# Paulo_V2.net
KiCad netlist of a schematic drawn in EAGLE
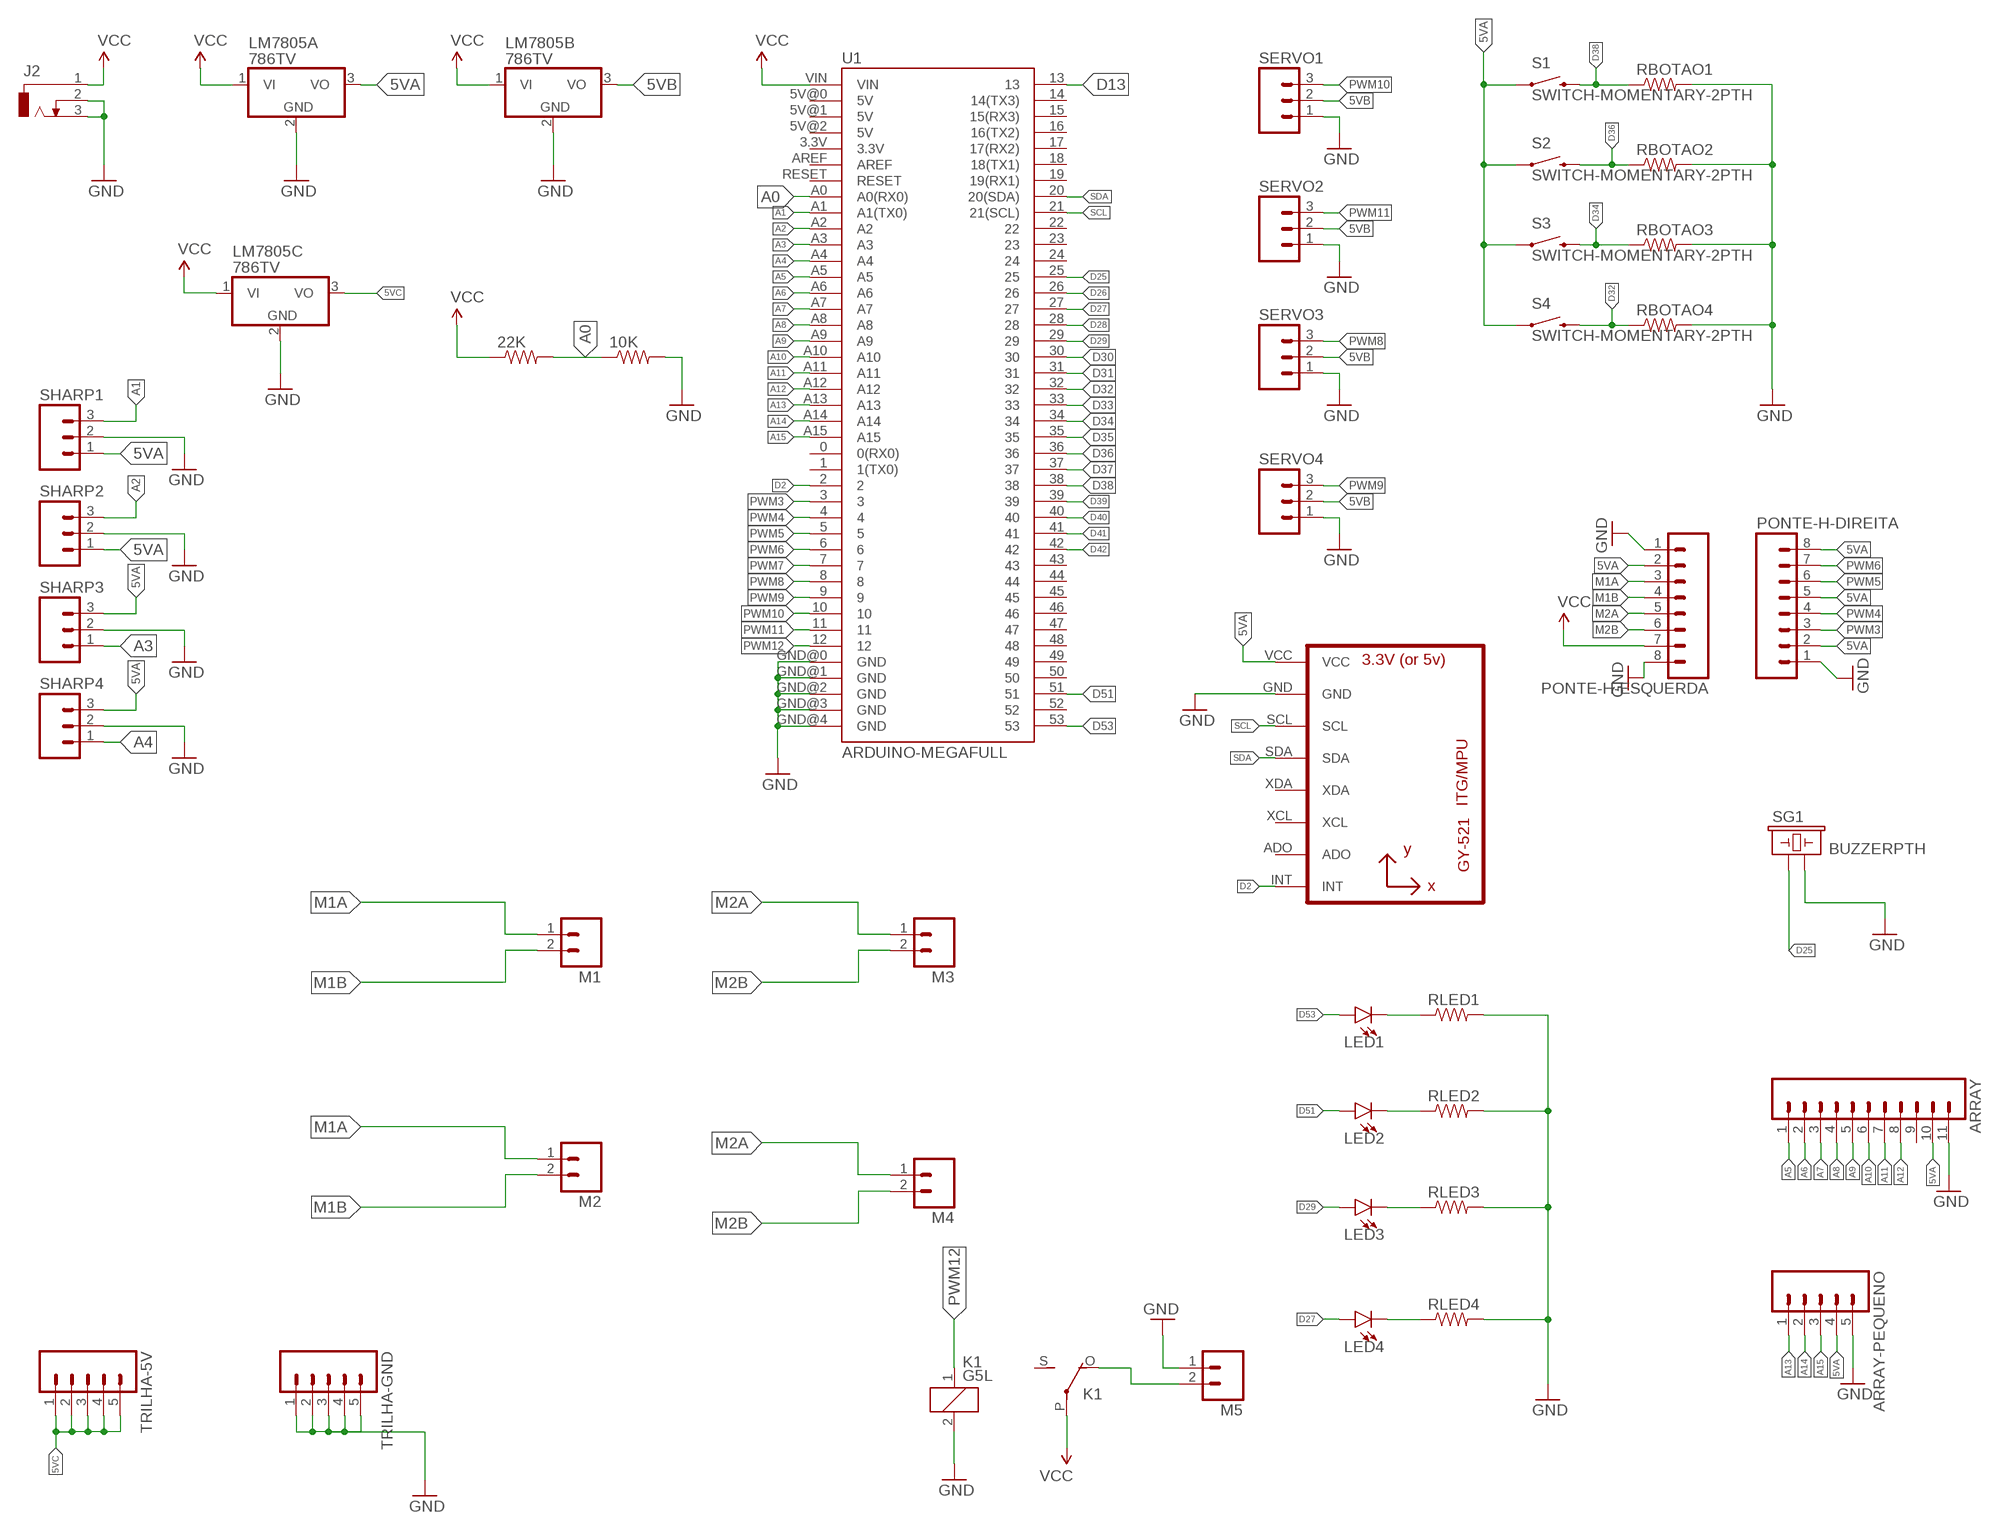
[diagram p0: schematic, sheet 1]

(export (version "E")
  (design (tool "Eeschema 10.0.6"))
  (components
    (comp (ref "10K")
      (value "RESISTOREZ")
      (footprint "eagle-import:AXIAL-0.3EZ")
      (libsource (lib "eagle-import") (part "RESISTOREZ"))
    )
    (comp (ref "22K")
      (value "RESISTOREZ")
      (footprint "eagle-import:AXIAL-0.3EZ")
      (libsource (lib "eagle-import") (part "RESISTOREZ"))
    )
    (comp (ref "ARRAY")
      (value "M11POGOPIN_HOLES_ONLY")
      (footprint "eagle-import:1X11_HOLES_ONLY")
      (libsource (lib "eagle-import") (part "M11POGOPIN_HOLES_ONLY"))
    )
    (comp (ref "ARRAY-PEQUENO")
      (value "M05PTH")
      (footprint "eagle-import:1X05")
      (libsource (lib "eagle-import") (part "M05PTH"))
    )
    (comp (ref "J2")
      (value "DCJ0303")
      (footprint "eagle-import:DCJ0303")
      (libsource (lib "eagle-import") (part "DCJ0303"))
    )
    (comp (ref "K1")
      (value "G5L")
      (footprint "eagle-import:G5LE")
      (libsource (lib "eagle-import") (part "G5L"))
    )
    (comp (ref "LED1")
      (value "LED5MM")
      (footprint "eagle-import:LED_5MM")
      (libsource (lib "eagle-import") (part "LED5MM"))
    )
    (comp (ref "LED2")
      (value "LED5MM")
      (footprint "eagle-import:LED_5MM")
      (libsource (lib "eagle-import") (part "LED5MM"))
    )
    (comp (ref "LED3")
      (value "LED5MM")
      (footprint "eagle-import:LED_5MM")
      (libsource (lib "eagle-import") (part "LED5MM"))
    )
    (comp (ref "LED4")
      (value "LED5MM")
      (footprint "eagle-import:LED_5MM")
      (libsource (lib "eagle-import") (part "LED5MM"))
    )
    (comp (ref "LM7805A")
      (value "786TV")
      (footprint "eagle-import:TO220V")
      (libsource (lib "eagle-import") (part "78TV6"))
    )
    (comp (ref "LM7805B")
      (value "786TV")
      (footprint "eagle-import:TO220V")
      (libsource (lib "eagle-import") (part "78TV6"))
    )
    (comp (ref "LM7805C")
      (value "786TV")
      (footprint "eagle-import:TO220V")
      (libsource (lib "eagle-import") (part "78TV6"))
    )
    (comp (ref "M1")
      (value "M02JST-PTH-VERT")
      (footprint "eagle-import:JST-2-PTH-VERT")
      (libsource (lib "eagle-import") (part "M02JST-PTH-VERT"))
    )
    (comp (ref "M2")
      (value "M02JST-PTH-VERT")
      (footprint "eagle-import:JST-2-PTH-VERT")
      (libsource (lib "eagle-import") (part "M02JST-PTH-VERT"))
    )
    (comp (ref "M3")
      (value "M02JST-PTH-VERT")
      (footprint "eagle-import:JST-2-PTH-VERT")
      (libsource (lib "eagle-import") (part "M02JST-PTH-VERT"))
    )
    (comp (ref "M4")
      (value "M02JST-PTH-VERT")
      (footprint "eagle-import:JST-2-PTH-VERT")
      (libsource (lib "eagle-import") (part "M02JST-PTH-VERT"))
    )
    (comp (ref "M5")
      (value "M02JST-PTH-VERT")
      (footprint "eagle-import:JST-2-PTH-VERT")
      (libsource (lib "eagle-import") (part "M02JST-PTH-VERT"))
    )
    (comp (ref "PONTE-H-DIREITA")
      (value "M08NO_SILK")
      (footprint "eagle-import:1X08_PIN1_NO_SILK")
      (libsource (lib "eagle-import") (part "M08NO_SILK"))
    )
    (comp (ref "PONTE-H-ESQUERDA")
      (value "M08NO_SILK")
      (footprint "eagle-import:1X08_PIN1_NO_SILK")
      (libsource (lib "eagle-import") (part "M08NO_SILK"))
    )
    (comp (ref "RBOTAO1")
      (value "RESISTOREZ")
      (footprint "eagle-import:AXIAL-0.3EZ")
      (libsource (lib "eagle-import") (part "RESISTOREZ"))
    )
    (comp (ref "RBOTAO2")
      (value "RESISTOREZ")
      (footprint "eagle-import:AXIAL-0.3EZ")
      (libsource (lib "eagle-import") (part "RESISTOREZ"))
    )
    (comp (ref "RBOTAO3")
      (value "RESISTOREZ")
      (footprint "eagle-import:AXIAL-0.3EZ")
      (libsource (lib "eagle-import") (part "RESISTOREZ"))
    )
    (comp (ref "RBOTAO4")
      (value "RESISTOREZ")
      (footprint "eagle-import:AXIAL-0.3EZ")
      (libsource (lib "eagle-import") (part "RESISTOREZ"))
    )
    (comp (ref "RLED1")
      (value "RESISTOREZ")
      (footprint "eagle-import:AXIAL-0.3EZ")
      (libsource (lib "eagle-import") (part "RESISTOREZ"))
    )
    (comp (ref "RLED2")
      (value "RESISTOREZ")
      (footprint "eagle-import:AXIAL-0.3EZ")
      (libsource (lib "eagle-import") (part "RESISTOREZ"))
    )
    (comp (ref "RLED3")
      (value "RESISTOREZ")
      (footprint "eagle-import:AXIAL-0.3EZ")
      (libsource (lib "eagle-import") (part "RESISTOREZ"))
    )
    (comp (ref "RLED4")
      (value "RESISTOREZ")
      (footprint "eagle-import:AXIAL-0.3EZ")
      (libsource (lib "eagle-import") (part "RESISTOREZ"))
    )
    (comp (ref "S1")
      (value "SWITCH-MOMENTARY-2PTH")
      (footprint "eagle-import:TACTILE-PTH")
      (libsource (lib "eagle-import") (part "SWITCH-MOMENTARY-2PTH"))
    )
    (comp (ref "S2")
      (value "SWITCH-MOMENTARY-2PTH")
      (footprint "eagle-import:TACTILE-PTH")
      (libsource (lib "eagle-import") (part "SWITCH-MOMENTARY-2PTH"))
    )
    (comp (ref "S3")
      (value "SWITCH-MOMENTARY-2PTH")
      (footprint "eagle-import:TACTILE-PTH")
      (libsource (lib "eagle-import") (part "SWITCH-MOMENTARY-2PTH"))
    )
    (comp (ref "S4")
      (value "SWITCH-MOMENTARY-2PTH")
      (footprint "eagle-import:TACTILE-PTH")
      (libsource (lib "eagle-import") (part "SWITCH-MOMENTARY-2PTH"))
    )
    (comp (ref "SERVO1")
      (value "M03LONGPADS")
      (footprint "eagle-import:1X03_LONGPADS@1")
      (libsource (lib "eagle-import") (part "M03LONGPADS"))
    )
    (comp (ref "SERVO2")
      (value "M03LONGPADS")
      (footprint "eagle-import:1X03_LONGPADS@1")
      (libsource (lib "eagle-import") (part "M03LONGPADS"))
    )
    (comp (ref "SERVO3")
      (value "M03LONGPADS")
      (footprint "eagle-import:1X03_LONGPADS@1")
      (libsource (lib "eagle-import") (part "M03LONGPADS"))
    )
    (comp (ref "SERVO4")
      (value "M03LONGPADS")
      (footprint "eagle-import:1X03_LONGPADS@1")
      (libsource (lib "eagle-import") (part "M03LONGPADS"))
    )
    (comp (ref "SG1")
      (value "BUZZERPTH")
      (footprint "eagle-import:BUZZER-12MM")
      (libsource (lib "eagle-import") (part "BUZZERPTH"))
    )
    (comp (ref "SHARP1")
      (value "M03LONGPADS")
      (footprint "eagle-import:1X03_LONGPADS@1")
      (libsource (lib "eagle-import") (part "M03LONGPADS"))
    )
    (comp (ref "SHARP2")
      (value "M03LONGPADS")
      (footprint "eagle-import:1X03_LONGPADS@1")
      (libsource (lib "eagle-import") (part "M03LONGPADS"))
    )
    (comp (ref "SHARP3")
      (value "M03LONGPADS")
      (footprint "eagle-import:1X03_LONGPADS@1")
      (libsource (lib "eagle-import") (part "M03LONGPADS"))
    )
    (comp (ref "SHARP4")
      (value "M03LONGPADS")
      (footprint "eagle-import:1X03_LONGPADS@1")
      (libsource (lib "eagle-import") (part "M03LONGPADS"))
    )
    (comp (ref "TRILHA-5V")
      (value "M05PTH")
      (footprint "eagle-import:1X05")
      (libsource (lib "eagle-import") (part "M05PTH"))
    )
    (comp (ref "TRILHA-GND")
      (value "M05PTH")
      (footprint "eagle-import:1X05")
      (libsource (lib "eagle-import") (part "M05PTH"))
    )
    (comp (ref "U1")
      (value "ARDUINO-MEGAFULL")
      (footprint "eagle-import:ARDUINO_MEGA")
      (libsource (lib "eagle-import") (part "ARDUINO-MEGAFULL"))
    )
    (comp (ref "U2")
      (value "GY-521MPU6050")
      (footprint "eagle-import:GY-521")
      (libsource (lib "eagle-import") (part "GY-521MPU6050"))
    )
  )
  (nets
    (net (code "1") (name "5VA") (class "Default")
      (node (ref "ARRAY") (pin "10") (pinfunction "10_10") (pintype "passive"))
      (node (ref "ARRAY-PEQUENO") (pin "4") (pinfunction "4_4") (pintype "passive"))
      (node (ref "LM7805A") (pin "3") (pinfunction "VO_3") (pintype "passive"))
      (node (ref "PONTE-H-DIREITA") (pin "2") (pinfunction "2_2") (pintype "passive"))
      (node (ref "PONTE-H-DIREITA") (pin "5") (pinfunction "5_5") (pintype "passive"))
      (node (ref "PONTE-H-DIREITA") (pin "8") (pinfunction "8_8") (pintype "passive"))
      (node (ref "PONTE-H-ESQUERDA") (pin "2") (pinfunction "2_2") (pintype "passive"))
      (node (ref "S1") (pin "1") (pinfunction "1_1") (pintype "passive"))
      (node (ref "S2") (pin "1") (pinfunction "1_1") (pintype "passive"))
      (node (ref "S3") (pin "1") (pinfunction "1_1") (pintype "passive"))
      (node (ref "S4") (pin "1") (pinfunction "1_1") (pintype "passive"))
      (node (ref "SHARP1") (pin "1") (pinfunction "1_1") (pintype "passive"))
      (node (ref "SHARP2") (pin "1") (pinfunction "1_1") (pintype "passive"))
      (node (ref "SHARP3") (pin "3") (pinfunction "3_3") (pintype "passive"))
      (node (ref "SHARP4") (pin "3") (pinfunction "3_3") (pintype "passive"))
      (node (ref "U2") (pin "VCC") (pinfunction "VCC_VCC") (pintype "bidirectional"))
    )
    (net (code "2") (name "5VB") (class "Default")
      (node (ref "LM7805B") (pin "3") (pinfunction "VO_3") (pintype "passive"))
      (node (ref "SERVO1") (pin "2") (pinfunction "2_2") (pintype "passive"))
      (node (ref "SERVO2") (pin "2") (pinfunction "2_2") (pintype "passive"))
      (node (ref "SERVO3") (pin "2") (pinfunction "2_2") (pintype "passive"))
      (node (ref "SERVO4") (pin "2") (pinfunction "2_2") (pintype "passive"))
    )
    (net (code "3") (name "5VC") (class "Default")
      (node (ref "LM7805C") (pin "3") (pinfunction "VO_3") (pintype "passive"))
      (node (ref "TRILHA-5V") (pin "1") (pinfunction "1_1") (pintype "passive"))
      (node (ref "TRILHA-5V") (pin "2") (pinfunction "2_2") (pintype "passive"))
      (node (ref "TRILHA-5V") (pin "3") (pinfunction "3_3") (pintype "passive"))
      (node (ref "TRILHA-5V") (pin "4") (pinfunction "4_4") (pintype "passive"))
      (node (ref "TRILHA-5V") (pin "5") (pinfunction "5_5") (pintype "passive"))
    )
    (net (code "4") (name "A0") (class "Default")
      (node (ref "10K") (pin "P$1") (pinfunction "1_P$1") (pintype "passive"))
      (node (ref "22K") (pin "P$2") (pinfunction "2_P$2") (pintype "passive"))
      (node (ref "U1") (pin "A0") (pinfunction "A0(RX0)_A0") (pintype "bidirectional"))
    )
    (net (code "5") (name "A1") (class "Default")
      (node (ref "SHARP1") (pin "3") (pinfunction "3_3") (pintype "passive"))
      (node (ref "U1") (pin "A1") (pinfunction "A1(TX0)_A1") (pintype "bidirectional"))
    )
    (net (code "6") (name "A2") (class "Default")
      (node (ref "SHARP2") (pin "3") (pinfunction "3_3") (pintype "passive"))
      (node (ref "U1") (pin "A2") (pinfunction "A2_A2") (pintype "bidirectional"))
    )
    (net (code "7") (name "A3") (class "Default")
      (node (ref "SHARP3") (pin "1") (pinfunction "1_1") (pintype "passive"))
      (node (ref "U1") (pin "A3") (pinfunction "A3_A3") (pintype "bidirectional"))
    )
    (net (code "8") (name "A4") (class "Default")
      (node (ref "SHARP4") (pin "1") (pinfunction "1_1") (pintype "passive"))
      (node (ref "U1") (pin "A4") (pinfunction "A4_A4") (pintype "bidirectional"))
    )
    (net (code "9") (name "A5") (class "Default")
      (node (ref "ARRAY") (pin "1") (pinfunction "1_1") (pintype "passive"))
      (node (ref "U1") (pin "A5") (pinfunction "A5_A5") (pintype "bidirectional"))
    )
    (net (code "10") (name "A6") (class "Default")
      (node (ref "ARRAY") (pin "2") (pinfunction "2_2") (pintype "passive"))
      (node (ref "U1") (pin "A6") (pinfunction "A6_A6") (pintype "bidirectional"))
    )
    (net (code "11") (name "A7") (class "Default")
      (node (ref "ARRAY") (pin "3") (pinfunction "3_3") (pintype "passive"))
      (node (ref "U1") (pin "A7") (pinfunction "A7_A7") (pintype "bidirectional"))
    )
    (net (code "12") (name "A8") (class "Default")
      (node (ref "ARRAY") (pin "4") (pinfunction "4_4") (pintype "passive"))
      (node (ref "U1") (pin "A8") (pinfunction "A8_A8") (pintype "bidirectional"))
    )
    (net (code "13") (name "A9") (class "Default")
      (node (ref "ARRAY") (pin "5") (pinfunction "5_5") (pintype "passive"))
      (node (ref "U1") (pin "A9") (pinfunction "A9_A9") (pintype "bidirectional"))
    )
    (net (code "14") (name "A10") (class "Default")
      (node (ref "ARRAY") (pin "6") (pinfunction "6_6") (pintype "passive"))
      (node (ref "U1") (pin "A10") (pinfunction "A10_A10") (pintype "bidirectional"))
    )
    (net (code "15") (name "A11") (class "Default")
      (node (ref "ARRAY") (pin "7") (pinfunction "7_7") (pintype "passive"))
      (node (ref "U1") (pin "A11") (pinfunction "A11_A11") (pintype "bidirectional"))
    )
    (net (code "16") (name "A12") (class "Default")
      (node (ref "ARRAY") (pin "8") (pinfunction "8_8") (pintype "passive"))
      (node (ref "U1") (pin "A12") (pinfunction "A12_A12") (pintype "bidirectional"))
    )
    (net (code "17") (name "A13") (class "Default")
      (node (ref "ARRAY-PEQUENO") (pin "1") (pinfunction "1_1") (pintype "passive"))
      (node (ref "U1") (pin "A13") (pinfunction "A13_A13") (pintype "bidirectional"))
    )
    (net (code "18") (name "A14") (class "Default")
      (node (ref "ARRAY-PEQUENO") (pin "2") (pinfunction "2_2") (pintype "passive"))
      (node (ref "U1") (pin "A14") (pinfunction "A14_A14") (pintype "bidirectional"))
    )
    (net (code "19") (name "A15") (class "Default")
      (node (ref "ARRAY-PEQUENO") (pin "3") (pinfunction "3_3") (pintype "passive"))
      (node (ref "U1") (pin "A15") (pinfunction "A15_A15") (pintype "bidirectional"))
    )
    (net (code "20") (name "D2") (class "Default")
      (node (ref "U1") (pin "2") (pinfunction "2_2") (pintype "bidirectional"))
      (node (ref "U2") (pin "INT") (pinfunction "INT_INT") (pintype "bidirectional"))
    )
    (net (code "21") (name "D13") (class "Default")
      (node (ref "U1") (pin "13") (pinfunction "13_13") (pintype "bidirectional"))
    )
    (net (code "22") (name "D25") (class "Default")
      (node (ref "SG1") (pin "+") (pinfunction "1_+") (pintype "passive"))
      (node (ref "U1") (pin "25") (pinfunction "25_25") (pintype "bidirectional"))
    )
    (net (code "23") (name "D26") (class "Default")
      (node (ref "U1") (pin "26") (pinfunction "26_26") (pintype "bidirectional"))
    )
    (net (code "24") (name "D27") (class "Default")
      (node (ref "LED4") (pin "A") (pinfunction "A_A") (pintype "passive"))
      (node (ref "U1") (pin "27") (pinfunction "27_27") (pintype "bidirectional"))
    )
    (net (code "25") (name "D28") (class "Default")
      (node (ref "U1") (pin "28") (pinfunction "28_28") (pintype "bidirectional"))
    )
    (net (code "26") (name "D29") (class "Default")
      (node (ref "LED3") (pin "A") (pinfunction "A_A") (pintype "passive"))
      (node (ref "U1") (pin "29") (pinfunction "29_29") (pintype "bidirectional"))
    )
    (net (code "27") (name "D30") (class "Default")
      (node (ref "U1") (pin "30") (pinfunction "30_30") (pintype "bidirectional"))
    )
    (net (code "28") (name "D31") (class "Default")
      (node (ref "U1") (pin "31") (pinfunction "31_31") (pintype "bidirectional"))
    )
    (net (code "29") (name "D32") (class "Default")
      (node (ref "RBOTAO4") (pin "P$1") (pinfunction "1_P$1") (pintype "passive"))
      (node (ref "S4") (pin "3") (pinfunction "2_3") (pintype "passive"))
      (node (ref "U1") (pin "32") (pinfunction "32_32") (pintype "bidirectional"))
    )
    (net (code "30") (name "D33") (class "Default")
      (node (ref "U1") (pin "33") (pinfunction "33_33") (pintype "bidirectional"))
    )
    (net (code "31") (name "D34") (class "Default")
      (node (ref "RBOTAO3") (pin "P$1") (pinfunction "1_P$1") (pintype "passive"))
      (node (ref "S3") (pin "3") (pinfunction "2_3") (pintype "passive"))
      (node (ref "U1") (pin "34") (pinfunction "34_34") (pintype "bidirectional"))
    )
    (net (code "32") (name "D35") (class "Default")
      (node (ref "U1") (pin "35") (pinfunction "35_35") (pintype "bidirectional"))
    )
    (net (code "33") (name "D36") (class "Default")
      (node (ref "RBOTAO2") (pin "P$1") (pinfunction "1_P$1") (pintype "passive"))
      (node (ref "S2") (pin "3") (pinfunction "2_3") (pintype "passive"))
      (node (ref "U1") (pin "36") (pinfunction "36_36") (pintype "bidirectional"))
    )
    (net (code "34") (name "D37") (class "Default")
      (node (ref "U1") (pin "37") (pinfunction "37_37") (pintype "bidirectional"))
    )
    (net (code "35") (name "D38") (class "Default")
      (node (ref "RBOTAO1") (pin "P$1") (pinfunction "1_P$1") (pintype "passive"))
      (node (ref "S1") (pin "3") (pinfunction "2_3") (pintype "passive"))
      (node (ref "U1") (pin "38") (pinfunction "38_38") (pintype "bidirectional"))
    )
    (net (code "36") (name "D39") (class "Default")
      (node (ref "U1") (pin "39") (pinfunction "39_39") (pintype "bidirectional"))
    )
    (net (code "37") (name "D40") (class "Default")
      (node (ref "U1") (pin "40") (pinfunction "40_40") (pintype "bidirectional"))
    )
    (net (code "38") (name "D41") (class "Default")
      (node (ref "U1") (pin "41") (pinfunction "41_41") (pintype "bidirectional"))
    )
    (net (code "39") (name "D42") (class "Default")
      (node (ref "U1") (pin "42") (pinfunction "42_42") (pintype "bidirectional"))
    )
    (net (code "40") (name "D51") (class "Default")
      (node (ref "LED2") (pin "A") (pinfunction "A_A") (pintype "passive"))
      (node (ref "U1") (pin "51") (pinfunction "51_51") (pintype "bidirectional"))
    )
    (net (code "41") (name "D53") (class "Default")
      (node (ref "LED1") (pin "A") (pinfunction "A_A") (pintype "passive"))
      (node (ref "U1") (pin "53") (pinfunction "53_53") (pintype "bidirectional"))
    )
    (net (code "42") (name "GND") (class "Default")
      (node (ref "10K") (pin "P$2") (pinfunction "2_P$2") (pintype "passive"))
      (node (ref "ARRAY") (pin "11") (pinfunction "11_11") (pintype "passive"))
      (node (ref "ARRAY-PEQUENO") (pin "5") (pinfunction "5_5") (pintype "passive"))
      (node (ref "J2") (pin "2") (pinfunction "2_2") (pintype "passive"))
      (node (ref "J2") (pin "3") (pinfunction "3_3") (pintype "passive"))
      (node (ref "K1") (pin "2") (pinfunction "2_2") (pintype "passive"))
      (node (ref "LM7805A") (pin "2") (pinfunction "GND_2") (pintype "passive"))
      (node (ref "LM7805B") (pin "2") (pinfunction "GND_2") (pintype "passive"))
      (node (ref "LM7805C") (pin "2") (pinfunction "GND_2") (pintype "passive"))
      (node (ref "M5") (pin "1") (pinfunction "1_1") (pintype "passive"))
      (node (ref "PONTE-H-DIREITA") (pin "1") (pinfunction "1_1") (pintype "passive"))
      (node (ref "PONTE-H-ESQUERDA") (pin "1") (pinfunction "1_1") (pintype "passive"))
      (node (ref "PONTE-H-ESQUERDA") (pin "8") (pinfunction "8_8") (pintype "passive"))
      (node (ref "RBOTAO1") (pin "P$2") (pinfunction "2_P$2") (pintype "passive"))
      (node (ref "RBOTAO2") (pin "P$2") (pinfunction "2_P$2") (pintype "passive"))
      (node (ref "RBOTAO3") (pin "P$2") (pinfunction "2_P$2") (pintype "passive"))
      (node (ref "RBOTAO4") (pin "P$2") (pinfunction "2_P$2") (pintype "passive"))
      (node (ref "RLED1") (pin "P$2") (pinfunction "2_P$2") (pintype "passive"))
      (node (ref "RLED2") (pin "P$2") (pinfunction "2_P$2") (pintype "passive"))
      (node (ref "RLED3") (pin "P$2") (pinfunction "2_P$2") (pintype "passive"))
      (node (ref "RLED4") (pin "P$2") (pinfunction "2_P$2") (pintype "passive"))
      (node (ref "SERVO1") (pin "1") (pinfunction "1_1") (pintype "passive"))
      (node (ref "SERVO2") (pin "1") (pinfunction "1_1") (pintype "passive"))
      (node (ref "SERVO3") (pin "1") (pinfunction "1_1") (pintype "passive"))
      (node (ref "SERVO4") (pin "1") (pinfunction "1_1") (pintype "passive"))
      (node (ref "SG1") (pin "-") (pinfunction "2_-") (pintype "passive"))
      (node (ref "SHARP1") (pin "2") (pinfunction "2_2") (pintype "passive"))
      (node (ref "SHARP2") (pin "2") (pinfunction "2_2") (pintype "passive"))
      (node (ref "SHARP3") (pin "2") (pinfunction "2_2") (pintype "passive"))
      (node (ref "SHARP4") (pin "2") (pinfunction "2_2") (pintype "passive"))
      (node (ref "TRILHA-GND") (pin "1") (pinfunction "1_1") (pintype "passive"))
      (node (ref "TRILHA-GND") (pin "2") (pinfunction "2_2") (pintype "passive"))
      (node (ref "TRILHA-GND") (pin "3") (pinfunction "3_3") (pintype "passive"))
      (node (ref "TRILHA-GND") (pin "4") (pinfunction "4_4") (pintype "passive"))
      (node (ref "TRILHA-GND") (pin "5") (pinfunction "5_5") (pintype "passive"))
      (node (ref "U1") (pin "GND@0") (pinfunction "GND_GND@0") (pintype "bidirectional"))
      (node (ref "U1") (pin "GND@1") (pinfunction "GND_GND@1") (pintype "bidirectional"))
      (node (ref "U1") (pin "GND@2") (pinfunction "GND_GND@2") (pintype "bidirectional"))
      (node (ref "U1") (pin "GND@3") (pinfunction "GND_GND@3") (pintype "bidirectional"))
      (node (ref "U1") (pin "GND@4") (pinfunction "GND_GND@4") (pintype "bidirectional"))
      (node (ref "U2") (pin "GND") (pinfunction "GND_GND") (pintype "bidirectional"))
    )
    (net (code "43") (name "M1A") (class "Default")
      (node (ref "M1") (pin "1") (pinfunction "1_1") (pintype "passive"))
      (node (ref "M2") (pin "1") (pinfunction "1_1") (pintype "passive"))
      (node (ref "PONTE-H-ESQUERDA") (pin "3") (pinfunction "3_3") (pintype "passive"))
    )
    (net (code "44") (name "M1B") (class "Default")
      (node (ref "M1") (pin "2") (pinfunction "2_2") (pintype "passive"))
      (node (ref "M2") (pin "2") (pinfunction "2_2") (pintype "passive"))
      (node (ref "PONTE-H-ESQUERDA") (pin "4") (pinfunction "4_4") (pintype "passive"))
    )
    (net (code "45") (name "M2A") (class "Default")
      (node (ref "M3") (pin "1") (pinfunction "1_1") (pintype "passive"))
      (node (ref "M4") (pin "1") (pinfunction "1_1") (pintype "passive"))
      (node (ref "PONTE-H-ESQUERDA") (pin "5") (pinfunction "5_5") (pintype "passive"))
    )
    (net (code "46") (name "M2B") (class "Default")
      (node (ref "M3") (pin "2") (pinfunction "2_2") (pintype "passive"))
      (node (ref "M4") (pin "2") (pinfunction "2_2") (pintype "passive"))
      (node (ref "PONTE-H-ESQUERDA") (pin "6") (pinfunction "6_6") (pintype "passive"))
    )
    (net (code "47") (name "Net-(K1-PadO)") (class "Default")
      (node (ref "K1") (pin "O") (pinfunction "O_O") (pintype "passive"))
      (node (ref "M5") (pin "2") (pinfunction "2_2") (pintype "passive"))
    )
    (net (code "48") (name "Net-(LED1-C)") (class "Default")
      (node (ref "LED1") (pin "K") (pinfunction "C_K") (pintype "passive"))
      (node (ref "RLED1") (pin "P$1") (pinfunction "1_P$1") (pintype "passive"))
    )
    (net (code "49") (name "Net-(LED2-C)") (class "Default")
      (node (ref "LED2") (pin "K") (pinfunction "C_K") (pintype "passive"))
      (node (ref "RLED2") (pin "P$1") (pinfunction "1_P$1") (pintype "passive"))
    )
    (net (code "50") (name "Net-(LED3-C)") (class "Default")
      (node (ref "LED3") (pin "K") (pinfunction "C_K") (pintype "passive"))
      (node (ref "RLED3") (pin "P$1") (pinfunction "1_P$1") (pintype "passive"))
    )
    (net (code "51") (name "Net-(LED4-C)") (class "Default")
      (node (ref "LED4") (pin "K") (pinfunction "C_K") (pintype "passive"))
      (node (ref "RLED4") (pin "P$1") (pinfunction "1_P$1") (pintype "passive"))
    )
    (net (code "52") (name "PWM3") (class "Default")
      (node (ref "PONTE-H-DIREITA") (pin "3") (pinfunction "3_3") (pintype "passive"))
      (node (ref "U1") (pin "3") (pinfunction "3_3") (pintype "bidirectional"))
    )
    (net (code "53") (name "PWM4") (class "Default")
      (node (ref "PONTE-H-DIREITA") (pin "4") (pinfunction "4_4") (pintype "passive"))
      (node (ref "U1") (pin "4") (pinfunction "4_4") (pintype "bidirectional"))
    )
    (net (code "54") (name "PWM5") (class "Default")
      (node (ref "PONTE-H-DIREITA") (pin "6") (pinfunction "6_6") (pintype "passive"))
      (node (ref "U1") (pin "5") (pinfunction "5_5") (pintype "bidirectional"))
    )
    (net (code "55") (name "PWM6") (class "Default")
      (node (ref "PONTE-H-DIREITA") (pin "7") (pinfunction "7_7") (pintype "passive"))
      (node (ref "U1") (pin "6") (pinfunction "6_6") (pintype "bidirectional"))
    )
    (net (code "56") (name "PWM7") (class "Default")
      (node (ref "U1") (pin "7") (pinfunction "7_7") (pintype "bidirectional"))
    )
    (net (code "57") (name "PWM8") (class "Default")
      (node (ref "SERVO3") (pin "3") (pinfunction "3_3") (pintype "passive"))
      (node (ref "U1") (pin "8") (pinfunction "8_8") (pintype "bidirectional"))
    )
    (net (code "58") (name "PWM9") (class "Default")
      (node (ref "SERVO4") (pin "3") (pinfunction "3_3") (pintype "passive"))
      (node (ref "U1") (pin "9") (pinfunction "9_9") (pintype "bidirectional"))
    )
    (net (code "59") (name "PWM10") (class "Default")
      (node (ref "SERVO1") (pin "3") (pinfunction "3_3") (pintype "passive"))
      (node (ref "U1") (pin "10") (pinfunction "10_10") (pintype "bidirectional"))
    )
    (net (code "60") (name "PWM11") (class "Default")
      (node (ref "SERVO2") (pin "3") (pinfunction "3_3") (pintype "passive"))
      (node (ref "U1") (pin "11") (pinfunction "11_11") (pintype "bidirectional"))
    )
    (net (code "61") (name "PWM12") (class "Default")
      (node (ref "K1") (pin "1") (pinfunction "1_1") (pintype "passive"))
      (node (ref "U1") (pin "12") (pinfunction "12_12") (pintype "bidirectional"))
    )
    (net (code "62") (name "SCL") (class "Default")
      (node (ref "U1") (pin "21") (pinfunction "21(SCL)_21") (pintype "bidirectional"))
      (node (ref "U2") (pin "SCL") (pinfunction "SCL_SCL") (pintype "bidirectional"))
    )
    (net (code "63") (name "SDA") (class "Default")
      (node (ref "U1") (pin "20") (pinfunction "20(SDA)_20") (pintype "bidirectional"))
      (node (ref "U2") (pin "SDA") (pinfunction "SDA_SDA") (pintype "bidirectional"))
    )
    (net (code "64") (name "VCC") (class "Default")
      (node (ref "22K") (pin "P$1") (pinfunction "1_P$1") (pintype "passive"))
      (node (ref "J2") (pin "1") (pinfunction "1_1") (pintype "passive"))
      (node (ref "K1") (pin "P") (pinfunction "P_P") (pintype "passive"))
      (node (ref "LM7805A") (pin "1") (pinfunction "VI_1") (pintype "input"))
      (node (ref "LM7805B") (pin "1") (pinfunction "VI_1") (pintype "input"))
      (node (ref "LM7805C") (pin "1") (pinfunction "VI_1") (pintype "input"))
      (node (ref "PONTE-H-ESQUERDA") (pin "7") (pinfunction "7_7") (pintype "passive"))
      (node (ref "U1") (pin "VIN") (pinfunction "VIN_VIN") (pintype "bidirectional"))
    )
    (net (code "65") (name "unconnected-(ARRAY-Pad9)") (class "Default")
      (node (ref "ARRAY") (pin "9") (pinfunction "9_9") (pintype "passive"))
    )
    (net (code "66") (name "unconnected-(K1-PadS)") (class "Default")
      (node (ref "K1") (pin "S") (pinfunction "S_S") (pintype "passive"))
    )
    (net (code "67") (name "unconnected-(U1-0(RX0)-Pad0)") (class "Default")
      (node (ref "U1") (pin "0") (pinfunction "0(RX0)_0") (pintype "bidirectional"))
    )
    (net (code "68") (name "unconnected-(U1-1(TX0)-Pad1)") (class "Default")
      (node (ref "U1") (pin "1") (pinfunction "1(TX0)_1") (pintype "bidirectional"))
    )
    (net (code "69") (name "unconnected-(U1-5V-Pad5V@0)") (class "Default")
      (node (ref "U1") (pin "5V@0") (pinfunction "5V_5V@0") (pintype "bidirectional"))
    )
    (net (code "70") (name "unconnected-(U1-5V-Pad5V@1)") (class "Default")
      (node (ref "U1") (pin "5V@1") (pinfunction "5V_5V@1") (pintype "bidirectional"))
    )
    (net (code "71") (name "unconnected-(U1-5V-Pad5V@2)") (class "Default")
      (node (ref "U1") (pin "5V@2") (pinfunction "5V_5V@2") (pintype "bidirectional"))
    )
    (net (code "72") (name "unconnected-(U1-14(TX3)-Pad14)") (class "Default")
      (node (ref "U1") (pin "14") (pinfunction "14(TX3)_14") (pintype "bidirectional"))
    )
    (net (code "73") (name "unconnected-(U1-15(RX3)-Pad15)") (class "Default")
      (node (ref "U1") (pin "15") (pinfunction "15(RX3)_15") (pintype "bidirectional"))
    )
    (net (code "74") (name "unconnected-(U1-16(TX2)-Pad16)") (class "Default")
      (node (ref "U1") (pin "16") (pinfunction "16(TX2)_16") (pintype "bidirectional"))
    )
    (net (code "75") (name "unconnected-(U1-17(RX2)-Pad17)") (class "Default")
      (node (ref "U1") (pin "17") (pinfunction "17(RX2)_17") (pintype "bidirectional"))
    )
    (net (code "76") (name "unconnected-(U1-18(TX1)-Pad18)") (class "Default")
      (node (ref "U1") (pin "18") (pinfunction "18(TX1)_18") (pintype "bidirectional"))
    )
    (net (code "77") (name "unconnected-(U1-19(RX1)-Pad19)") (class "Default")
      (node (ref "U1") (pin "19") (pinfunction "19(RX1)_19") (pintype "bidirectional"))
    )
    (net (code "78") (name "unconnected-(U1-Pad3.3V)") (class "Default")
      (node (ref "U1") (pin "3.3V") (pinfunction "3.3V_3.3V") (pintype "bidirectional"))
    )
    (net (code "79") (name "unconnected-(U1-Pad22)") (class "Default")
      (node (ref "U1") (pin "22") (pinfunction "22_22") (pintype "bidirectional"))
    )
    (net (code "80") (name "unconnected-(U1-Pad23)") (class "Default")
      (node (ref "U1") (pin "23") (pinfunction "23_23") (pintype "bidirectional"))
    )
    (net (code "81") (name "unconnected-(U1-Pad24)") (class "Default")
      (node (ref "U1") (pin "24") (pinfunction "24_24") (pintype "bidirectional"))
    )
    (net (code "82") (name "unconnected-(U1-Pad43)") (class "Default")
      (node (ref "U1") (pin "43") (pinfunction "43_43") (pintype "bidirectional"))
    )
    (net (code "83") (name "unconnected-(U1-Pad44)") (class "Default")
      (node (ref "U1") (pin "44") (pinfunction "44_44") (pintype "bidirectional"))
    )
    (net (code "84") (name "unconnected-(U1-Pad45)") (class "Default")
      (node (ref "U1") (pin "45") (pinfunction "45_45") (pintype "bidirectional"))
    )
    (net (code "85") (name "unconnected-(U1-Pad46)") (class "Default")
      (node (ref "U1") (pin "46") (pinfunction "46_46") (pintype "bidirectional"))
    )
    (net (code "86") (name "unconnected-(U1-Pad47)") (class "Default")
      (node (ref "U1") (pin "47") (pinfunction "47_47") (pintype "bidirectional"))
    )
    (net (code "87") (name "unconnected-(U1-Pad48)") (class "Default")
      (node (ref "U1") (pin "48") (pinfunction "48_48") (pintype "bidirectional"))
    )
    (net (code "88") (name "unconnected-(U1-Pad49)") (class "Default")
      (node (ref "U1") (pin "49") (pinfunction "49_49") (pintype "bidirectional"))
    )
    (net (code "89") (name "unconnected-(U1-Pad50)") (class "Default")
      (node (ref "U1") (pin "50") (pinfunction "50_50") (pintype "bidirectional"))
    )
    (net (code "90") (name "unconnected-(U1-Pad52)") (class "Default")
      (node (ref "U1") (pin "52") (pinfunction "52_52") (pintype "bidirectional"))
    )
    (net (code "91") (name "unconnected-(U1-PadAREF)") (class "Default")
      (node (ref "U1") (pin "AREF") (pinfunction "AREF_AREF") (pintype "bidirectional"))
    )
    (net (code "92") (name "unconnected-(U1-PadRESET)") (class "Default")
      (node (ref "U1") (pin "RESET") (pinfunction "RESET_RESET") (pintype "bidirectional"))
    )
    (net (code "93") (name "unconnected-(U2-PadADO)") (class "Default")
      (node (ref "U2") (pin "ADO") (pinfunction "ADO_ADO") (pintype "bidirectional"))
    )
    (net (code "94") (name "unconnected-(U2-PadXCL)") (class "Default")
      (node (ref "U2") (pin "XCL") (pinfunction "XCL_XCL") (pintype "bidirectional"))
    )
    (net (code "95") (name "unconnected-(U2-PadXDA)") (class "Default")
      (node (ref "U2") (pin "XDA") (pinfunction "XDA_XDA") (pintype "bidirectional"))
    )
  )
)
